# A4988_Definitivo.net
KiCad netlist of a schematic drawn in EAGLE
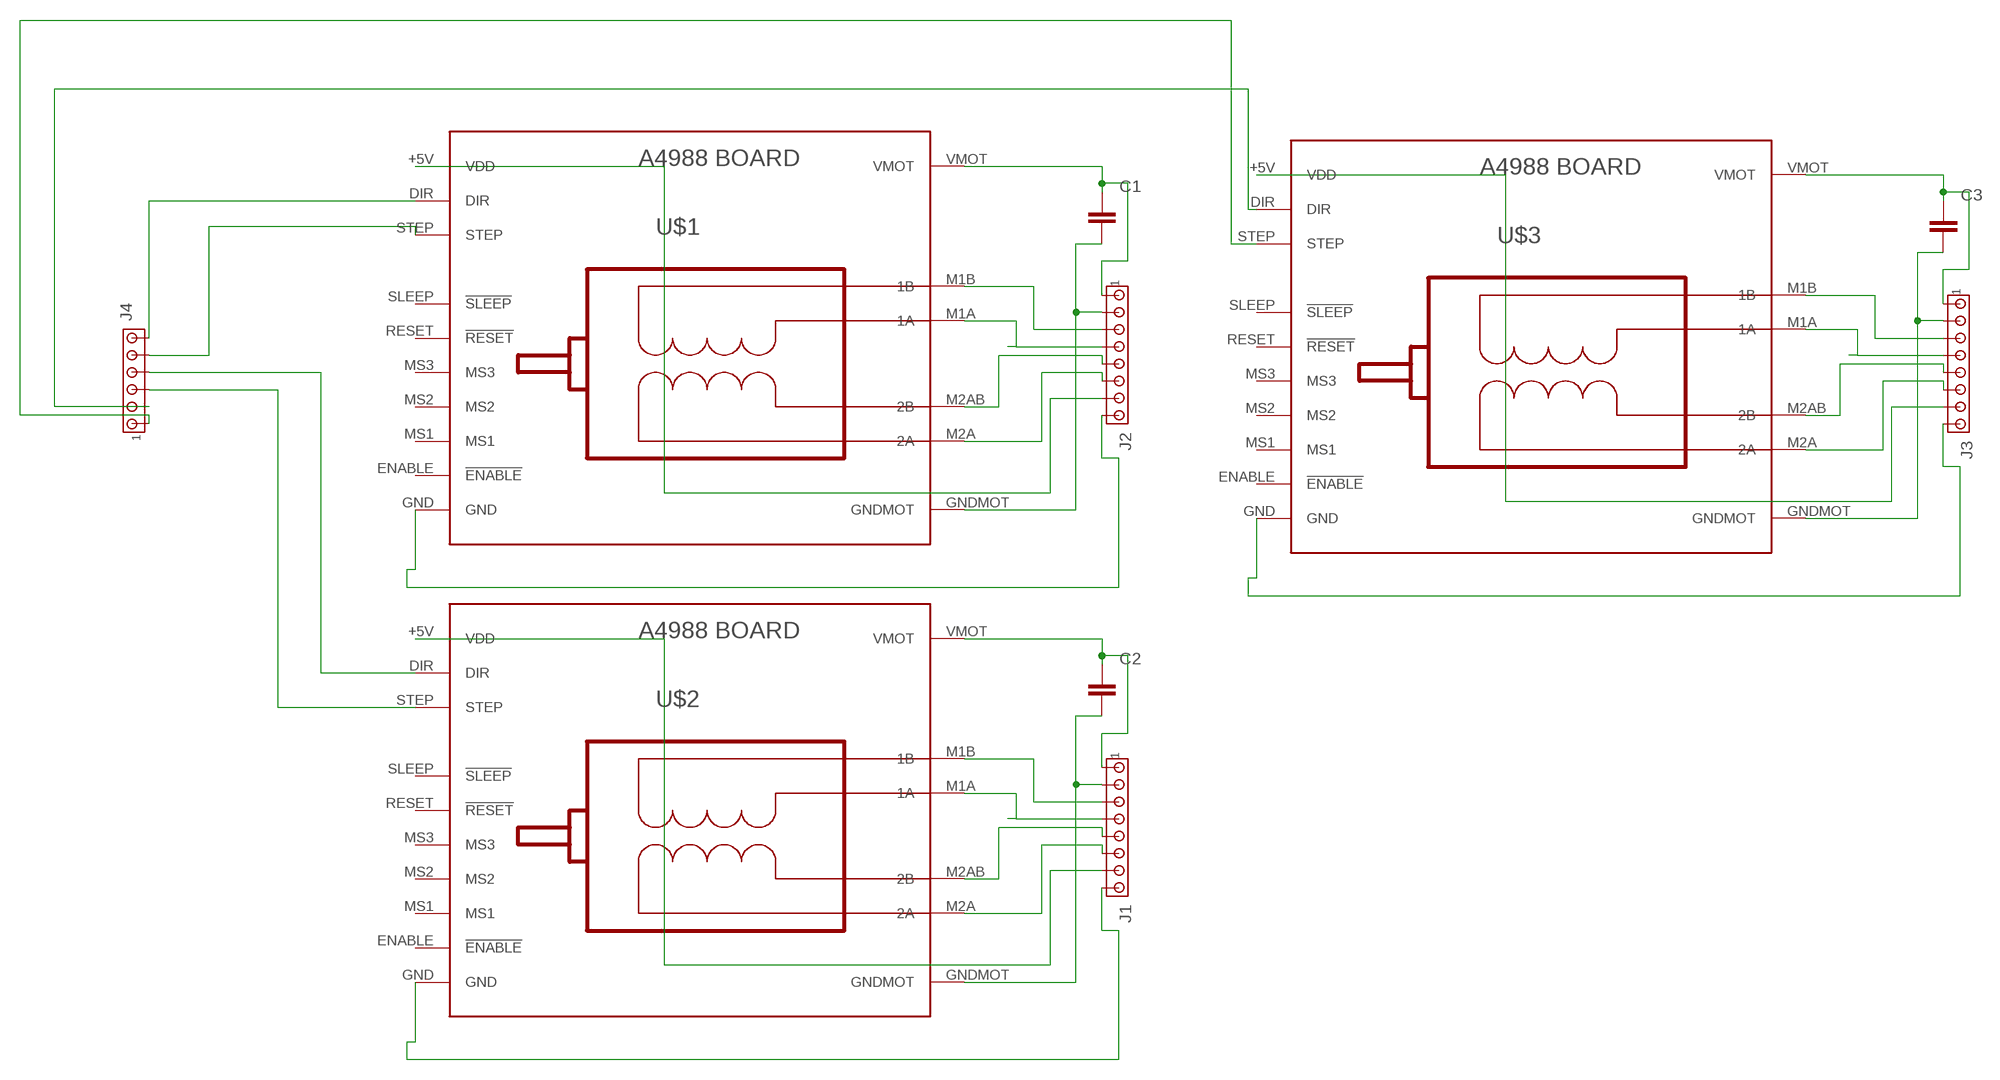
[diagram p0: schematic, sheet 1]

(export (version "E")
  (design (tool "Eeschema 10.0.6"))
  (components
    (comp (ref "C1")
      (value "C_RADIAL-12.5MM-DIA")
      (footprint "eagle-import:CAPRD550W60D1025H1250B")
      (libsource (lib "eagle-import") (part "CRADIAL-12.5MM-DIA_"))
    )
    (comp (ref "C2")
      (value "C_RADIAL-12.5MM-DIA")
      (footprint "eagle-import:CAPRD550W60D1025H1250B")
      (libsource (lib "eagle-import") (part "CRADIAL-12.5MM-DIA_"))
    )
    (comp (ref "C3")
      (value "C_RADIAL-12.5MM-DIA")
      (footprint "eagle-import:CAPRD550W60D1025H1250B")
      (libsource (lib "eagle-import") (part "CRADIAL-12.5MM-DIA_"))
    )
    (comp (ref "J1")
      (value "MTA08-100")
      (footprint "eagle-import:10X08MTA")
      (libsource (lib "eagle-import") (part "MTA08-100"))
    )
    (comp (ref "J2")
      (value "MTA08-100")
      (footprint "eagle-import:10X08MTA")
      (libsource (lib "eagle-import") (part "MTA08-100"))
    )
    (comp (ref "J3")
      (value "MTA08-100")
      (footprint "eagle-import:10X08MTA")
      (libsource (lib "eagle-import") (part "MTA08-100"))
    )
    (comp (ref "J4")
      (value "MTA06-156")
      (footprint "eagle-import:1X6MTA")
      (libsource (lib "eagle-import") (part "MTA06-156"))
    )
    (comp (ref "U$1")
      (value "BOARD_A4988")
      (footprint "eagle-import:BOARD_A4988")
      (libsource (lib "eagle-import") (part "BOARD_A4988"))
    )
    (comp (ref "U$2")
      (value "BOARD_A4988")
      (footprint "eagle-import:BOARD_A4988")
      (libsource (lib "eagle-import") (part "BOARD_A4988"))
    )
    (comp (ref "U$3")
      (value "BOARD_A4988")
      (footprint "eagle-import:BOARD_A4988")
      (libsource (lib "eagle-import") (part "BOARD_A4988"))
    )
  )
  (nets
    (net (code "1") (name "Net-(C1-Pad1)") (class "Default")
      (node (ref "C1") (pin "1") (pinfunction "1_1") (pintype "passive"))
      (node (ref "J2") (pin "1") (pinfunction "1_1") (pintype "passive"))
      (node (ref "U$1") (pin "VMOT") (pinfunction "VMOT_VMOT") (pintype "power_in"))
    )
    (net (code "2") (name "Net-(C1-Pad2)") (class "Default")
      (node (ref "C1") (pin "2") (pinfunction "2_2") (pintype "passive"))
      (node (ref "J2") (pin "2") (pinfunction "2_2") (pintype "passive"))
      (node (ref "U$1") (pin "GNDMOT") (pinfunction "GNDMOT_GNDMOT") (pintype "power_in"))
    )
    (net (code "3") (name "Net-(C2-Pad1)") (class "Default")
      (node (ref "C2") (pin "1") (pinfunction "1_1") (pintype "passive"))
      (node (ref "J1") (pin "1") (pinfunction "1_1") (pintype "passive"))
      (node (ref "U$2") (pin "VMOT") (pinfunction "VMOT_VMOT") (pintype "power_in"))
    )
    (net (code "4") (name "Net-(C2-Pad2)") (class "Default")
      (node (ref "C2") (pin "2") (pinfunction "2_2") (pintype "passive"))
      (node (ref "J1") (pin "2") (pinfunction "2_2") (pintype "passive"))
      (node (ref "U$2") (pin "GNDMOT") (pinfunction "GNDMOT_GNDMOT") (pintype "power_in"))
    )
    (net (code "5") (name "Net-(C3-Pad1)") (class "Default")
      (node (ref "C3") (pin "1") (pinfunction "1_1") (pintype "passive"))
      (node (ref "J3") (pin "1") (pinfunction "1_1") (pintype "passive"))
      (node (ref "U$3") (pin "VMOT") (pinfunction "VMOT_VMOT") (pintype "power_in"))
    )
    (net (code "6") (name "Net-(C3-Pad2)") (class "Default")
      (node (ref "C3") (pin "2") (pinfunction "2_2") (pintype "passive"))
      (node (ref "J3") (pin "2") (pinfunction "2_2") (pintype "passive"))
      (node (ref "U$3") (pin "GNDMOT") (pinfunction "GNDMOT_GNDMOT") (pintype "power_in"))
    )
    (net (code "7") (name "Net-(J1-Pad8)") (class "Default")
      (node (ref "J1") (pin "8") (pinfunction "8_8") (pintype "passive"))
      (node (ref "U$2") (pin "GND") (pinfunction "GND_GND") (pintype "power_in"))
    )
    (net (code "8") (name "Net-(J2-Pad8)") (class "Default")
      (node (ref "J2") (pin "8") (pinfunction "8_8") (pintype "passive"))
      (node (ref "U$1") (pin "GND") (pinfunction "GND_GND") (pintype "power_in"))
    )
    (net (code "9") (name "Net-(J3-Pad8)") (class "Default")
      (node (ref "J3") (pin "8") (pinfunction "8_8") (pintype "passive"))
      (node (ref "U$3") (pin "GND") (pinfunction "GND_GND") (pintype "power_in"))
    )
    (net (code "10") (name "Net-(J4-Pad1)") (class "Default")
      (node (ref "J4") (pin "1") (pinfunction "1_1") (pintype "passive"))
      (node (ref "U$3") (pin "STEP") (pinfunction "STEP_STEP") (pintype "input"))
    )
    (net (code "11") (name "Net-(J4-Pad2)") (class "Default")
      (node (ref "J4") (pin "2") (pinfunction "2_2") (pintype "passive"))
      (node (ref "U$3") (pin "DIR") (pinfunction "DIR_DIR") (pintype "input"))
    )
    (net (code "12") (name "Net-(J4-Pad3)") (class "Default")
      (node (ref "J4") (pin "3") (pinfunction "3_3") (pintype "passive"))
      (node (ref "U$2") (pin "STEP") (pinfunction "STEP_STEP") (pintype "input"))
    )
    (net (code "13") (name "Net-(J4-Pad4)") (class "Default")
      (node (ref "J4") (pin "4") (pinfunction "4_4") (pintype "passive"))
      (node (ref "U$2") (pin "DIR") (pinfunction "DIR_DIR") (pintype "input"))
    )
    (net (code "14") (name "Net-(J4-Pad5)") (class "Default")
      (node (ref "J4") (pin "5") (pinfunction "5_5") (pintype "passive"))
      (node (ref "U$1") (pin "STEP") (pinfunction "STEP_STEP") (pintype "input"))
    )
    (net (code "15") (name "Net-(J4-Pad6)") (class "Default")
      (node (ref "J4") (pin "6") (pinfunction "6_6") (pintype "passive"))
      (node (ref "U$1") (pin "DIR") (pinfunction "DIR_DIR") (pintype "input"))
    )
    (net (code "16") (name "Net-(U$1-1A)") (class "Default")
      (node (ref "J2") (pin "4") (pinfunction "4_4") (pintype "passive"))
      (node (ref "U$1") (pin "M1A") (pinfunction "1A_M1A") (pintype "output"))
    )
    (net (code "17") (name "Net-(U$1-1B)") (class "Default")
      (node (ref "J2") (pin "3") (pinfunction "3_3") (pintype "passive"))
      (node (ref "U$1") (pin "M1B") (pinfunction "1B_M1B") (pintype "output"))
    )
    (net (code "18") (name "Net-(U$1-2A)") (class "Default")
      (node (ref "J2") (pin "6") (pinfunction "6_6") (pintype "passive"))
      (node (ref "U$1") (pin "M2A") (pinfunction "2A_M2A") (pintype "output"))
    )
    (net (code "19") (name "Net-(U$1-2B)") (class "Default")
      (node (ref "J2") (pin "5") (pinfunction "5_5") (pintype "passive"))
      (node (ref "U$1") (pin "M2AB") (pinfunction "2B_M2AB") (pintype "output"))
    )
    (net (code "20") (name "Net-(U$1-VDD)") (class "Default")
      (node (ref "J2") (pin "7") (pinfunction "7_7") (pintype "passive"))
      (node (ref "U$1") (pin "+5V") (pinfunction "VDD_+5V") (pintype "power_in"))
    )
    (net (code "21") (name "Net-(U$2-1A)") (class "Default")
      (node (ref "J1") (pin "4") (pinfunction "4_4") (pintype "passive"))
      (node (ref "U$2") (pin "M1A") (pinfunction "1A_M1A") (pintype "output"))
    )
    (net (code "22") (name "Net-(U$2-1B)") (class "Default")
      (node (ref "J1") (pin "3") (pinfunction "3_3") (pintype "passive"))
      (node (ref "U$2") (pin "M1B") (pinfunction "1B_M1B") (pintype "output"))
    )
    (net (code "23") (name "Net-(U$2-2A)") (class "Default")
      (node (ref "J1") (pin "6") (pinfunction "6_6") (pintype "passive"))
      (node (ref "U$2") (pin "M2A") (pinfunction "2A_M2A") (pintype "output"))
    )
    (net (code "24") (name "Net-(U$2-2B)") (class "Default")
      (node (ref "J1") (pin "5") (pinfunction "5_5") (pintype "passive"))
      (node (ref "U$2") (pin "M2AB") (pinfunction "2B_M2AB") (pintype "output"))
    )
    (net (code "25") (name "Net-(U$2-VDD)") (class "Default")
      (node (ref "J1") (pin "7") (pinfunction "7_7") (pintype "passive"))
      (node (ref "U$2") (pin "+5V") (pinfunction "VDD_+5V") (pintype "power_in"))
    )
    (net (code "26") (name "Net-(U$3-1A)") (class "Default")
      (node (ref "J3") (pin "4") (pinfunction "4_4") (pintype "passive"))
      (node (ref "U$3") (pin "M1A") (pinfunction "1A_M1A") (pintype "output"))
    )
    (net (code "27") (name "Net-(U$3-1B)") (class "Default")
      (node (ref "J3") (pin "3") (pinfunction "3_3") (pintype "passive"))
      (node (ref "U$3") (pin "M1B") (pinfunction "1B_M1B") (pintype "output"))
    )
    (net (code "28") (name "Net-(U$3-2A)") (class "Default")
      (node (ref "J3") (pin "6") (pinfunction "6_6") (pintype "passive"))
      (node (ref "U$3") (pin "M2A") (pinfunction "2A_M2A") (pintype "output"))
    )
    (net (code "29") (name "Net-(U$3-2B)") (class "Default")
      (node (ref "J3") (pin "5") (pinfunction "5_5") (pintype "passive"))
      (node (ref "U$3") (pin "M2AB") (pinfunction "2B_M2AB") (pintype "output"))
    )
    (net (code "30") (name "Net-(U$3-VDD)") (class "Default")
      (node (ref "J3") (pin "7") (pinfunction "7_7") (pintype "passive"))
      (node (ref "U$3") (pin "+5V") (pinfunction "VDD_+5V") (pintype "power_in"))
    )
    (net (code "31") (name "unconnected-(U$1-PadMS1)") (class "Default")
      (node (ref "U$1") (pin "MS1") (pinfunction "MS1_MS1") (pintype "input"))
    )
    (net (code "32") (name "unconnected-(U$1-PadMS2)") (class "Default")
      (node (ref "U$1") (pin "MS2") (pinfunction "MS2_MS2") (pintype "input"))
    )
    (net (code "33") (name "unconnected-(U$1-PadMS3)") (class "Default")
      (node (ref "U$1") (pin "MS3") (pinfunction "MS3_MS3") (pintype "input"))
    )
    (net (code "34") (name "unconnected-(U$1-~{ENABLE}-PadENABLE)") (class "Default")
      (node (ref "U$1") (pin "ENABLE") (pinfunction "~{ENABLE}_ENABLE") (pintype "input"))
    )
    (net (code "35") (name "unconnected-(U$1-~{RESET}-PadRESET)") (class "Default")
      (node (ref "U$1") (pin "RESET") (pinfunction "~{RESET}_RESET") (pintype "input"))
    )
    (net (code "36") (name "unconnected-(U$1-~{SLEEP}-PadSLEEP)") (class "Default")
      (node (ref "U$1") (pin "SLEEP") (pinfunction "~{SLEEP}_SLEEP") (pintype "input"))
    )
    (net (code "37") (name "unconnected-(U$2-PadMS1)") (class "Default")
      (node (ref "U$2") (pin "MS1") (pinfunction "MS1_MS1") (pintype "input"))
    )
    (net (code "38") (name "unconnected-(U$2-PadMS2)") (class "Default")
      (node (ref "U$2") (pin "MS2") (pinfunction "MS2_MS2") (pintype "input"))
    )
    (net (code "39") (name "unconnected-(U$2-PadMS3)") (class "Default")
      (node (ref "U$2") (pin "MS3") (pinfunction "MS3_MS3") (pintype "input"))
    )
    (net (code "40") (name "unconnected-(U$2-~{ENABLE}-PadENABLE)") (class "Default")
      (node (ref "U$2") (pin "ENABLE") (pinfunction "~{ENABLE}_ENABLE") (pintype "input"))
    )
    (net (code "41") (name "unconnected-(U$2-~{RESET}-PadRESET)") (class "Default")
      (node (ref "U$2") (pin "RESET") (pinfunction "~{RESET}_RESET") (pintype "input"))
    )
    (net (code "42") (name "unconnected-(U$2-~{SLEEP}-PadSLEEP)") (class "Default")
      (node (ref "U$2") (pin "SLEEP") (pinfunction "~{SLEEP}_SLEEP") (pintype "input"))
    )
    (net (code "43") (name "unconnected-(U$3-PadMS1)") (class "Default")
      (node (ref "U$3") (pin "MS1") (pinfunction "MS1_MS1") (pintype "input"))
    )
    (net (code "44") (name "unconnected-(U$3-PadMS2)") (class "Default")
      (node (ref "U$3") (pin "MS2") (pinfunction "MS2_MS2") (pintype "input"))
    )
    (net (code "45") (name "unconnected-(U$3-PadMS3)") (class "Default")
      (node (ref "U$3") (pin "MS3") (pinfunction "MS3_MS3") (pintype "input"))
    )
    (net (code "46") (name "unconnected-(U$3-~{ENABLE}-PadENABLE)") (class "Default")
      (node (ref "U$3") (pin "ENABLE") (pinfunction "~{ENABLE}_ENABLE") (pintype "input"))
    )
    (net (code "47") (name "unconnected-(U$3-~{RESET}-PadRESET)") (class "Default")
      (node (ref "U$3") (pin "RESET") (pinfunction "~{RESET}_RESET") (pintype "input"))
    )
    (net (code "48") (name "unconnected-(U$3-~{SLEEP}-PadSLEEP)") (class "Default")
      (node (ref "U$3") (pin "SLEEP") (pinfunction "~{SLEEP}_SLEEP") (pintype "input"))
    )
  )
)
